# msp430.net
KiCad netlist of a schematic drawn in Altium Designer
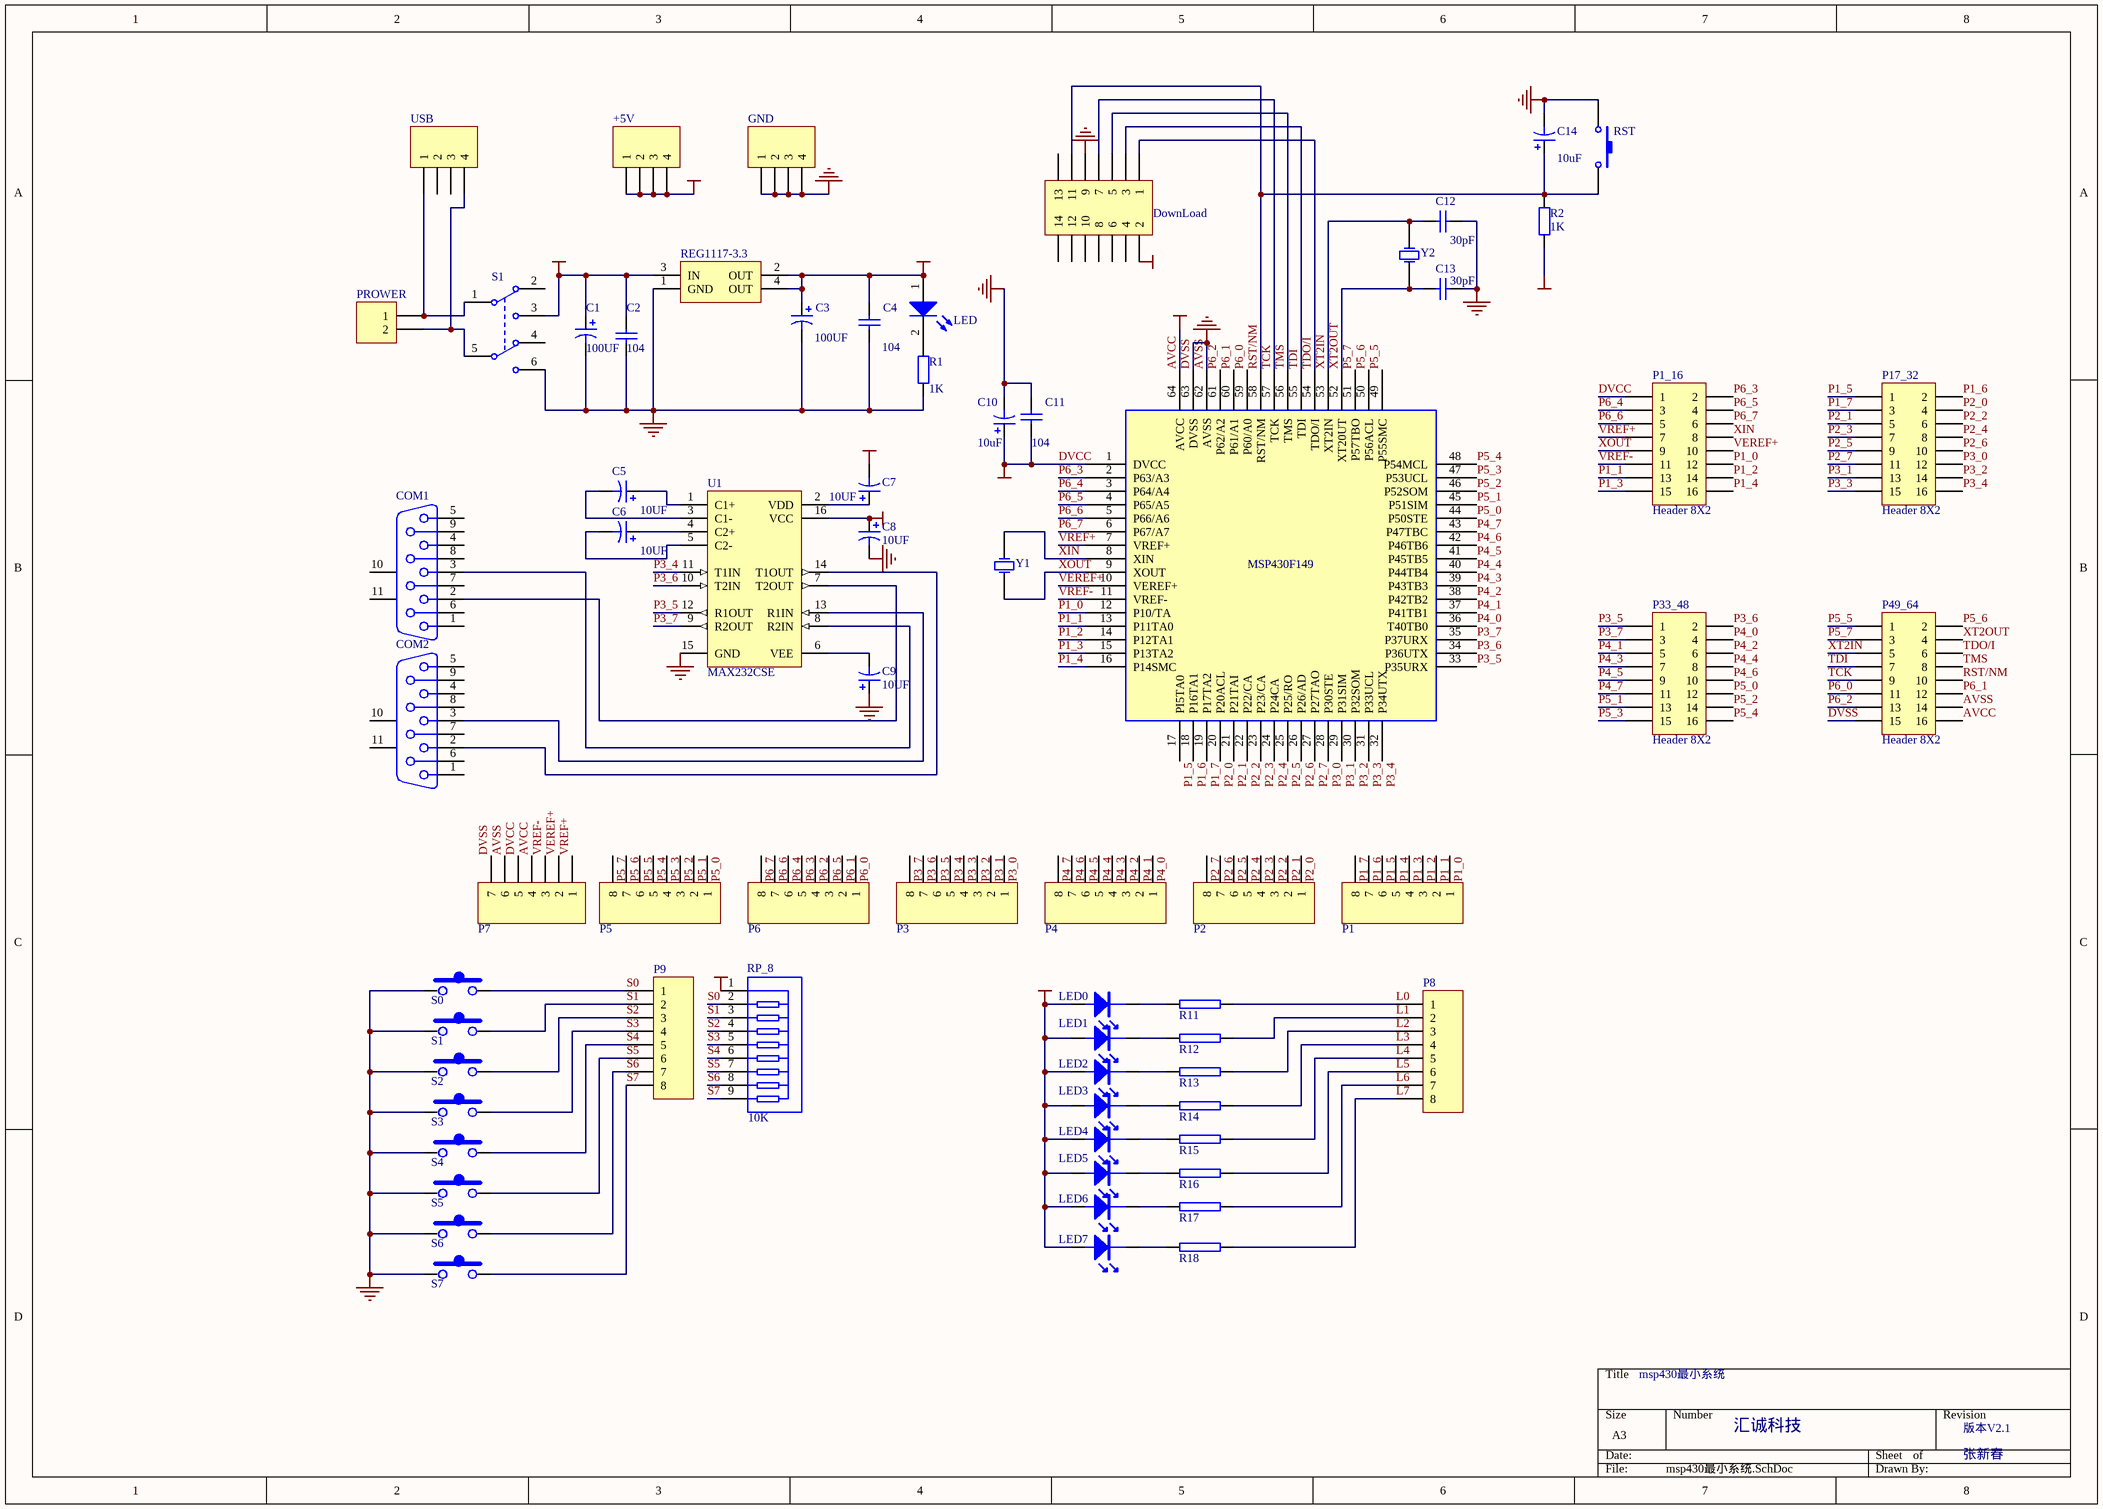
[diagram p0: msp430最小系统.SchDoc]

(export (version "E")
  (design (tool "Eeschema 10.0.6"))
  (components
    (comp (ref "+5V")
      (value "Header 4")
      (footprint "HDR1X4")
      (description "Header, 4-Pin")
      (fields (field (name "PUBLISHER") "Altium Limited"))
      (libsource (lib "Miscellaneous Connectors") (part "Header 4"))
    )
    (comp (ref "1") (value "S0") (footprint "an-6*6") (libsource (lib "OldCow1 (1)") (part "KEY")))
    (comp (ref "2") (value "S1") (footprint "an-6*6") (libsource (lib "OldCow1 (1)") (part "KEY")))
    (comp (ref "3") (value "S2") (footprint "an-6*6") (libsource (lib "OldCow1 (1)") (part "KEY")))
    (comp (ref "4") (value "S3") (footprint "an-6*6") (libsource (lib "OldCow1 (1)") (part "KEY")))
    (comp (ref "5") (value "S4") (footprint "an-6*6") (libsource (lib "OldCow1 (1)") (part "KEY")))
    (comp (ref "6") (value "S5") (footprint "an-6*6") (libsource (lib "OldCow1 (1)") (part "KEY")))
    (comp (ref "7") (value "S6") (footprint "an-6*6") (libsource (lib "OldCow1 (1)") (part "KEY")))
    (comp (ref "8") (value "S7") (footprint "an-6*6") (libsource (lib "OldCow1 (1)") (part "KEY")))
    (comp (ref "C1")
      (value "100UF")
      (footprint "C-DJ-6")
      (description "Polarized Capacitor (Radial)")
      (fields (field (name "Comment") "Cap Pol1") (field (name "PUBLISHER") "Altium Limited"))
      (libsource (lib "Miscellaneous Devices") (part "Cap Pol1"))
    )
    (comp (ref "C2")
      (value "104")
      (footprint "CPDR")
      (description "Capacitor (Semiconductor SIM Model)")
      (fields (field (name "Comment") "Cap Semi") (field (name "PUBLISHER") "Altium Limited"))
      (libsource (lib "Miscellaneous Devices") (part "Cap Semi"))
    )
    (comp (ref "C3")
      (value "100UF")
      (footprint "C-DJ-4")
      (description "Polarized Capacitor (Radial)")
      (fields (field (name "Comment") "Cap Pol1") (field (name "PUBLISHER") "Altium Limited"))
      (libsource (lib "Miscellaneous Devices") (part "Cap Pol1"))
    )
    (comp (ref "C4")
      (value "104")
      (footprint "CPDR")
      (description "Capacitor (Semiconductor SIM Model)")
      (fields (field (name "Comment") "Cap Semi") (field (name "PUBLISHER") "Altium Limited"))
      (libsource (lib "Miscellaneous Devices") (part "Cap Semi"))
    )
    (comp (ref "C5")
      (value "10UF")
      (footprint "C-DJ-4")
      (description "Polarized Capacitor (Radial)")
      (fields (field (name "Comment") "Cap Pol1") (field (name "PUBLISHER") "Altium Limited"))
      (libsource (lib "Miscellaneous Devices") (part "Cap Pol1"))
    )
    (comp (ref "C6")
      (value "10UF")
      (footprint "C-DJ-4")
      (description "Polarized Capacitor (Radial)")
      (fields (field (name "Comment") "Cap Pol1") (field (name "PUBLISHER") "Altium Limited"))
      (libsource (lib "Miscellaneous Devices") (part "Cap Pol1"))
    )
    (comp (ref "C7")
      (value "10UF")
      (footprint "C-DJ-4")
      (description "Polarized Capacitor (Radial)")
      (fields (field (name "Comment") "Cap Pol1") (field (name "PUBLISHER") "Altium Limited"))
      (libsource (lib "Miscellaneous Devices") (part "Cap Pol1"))
    )
    (comp (ref "C8")
      (value "10UF")
      (footprint "C-DJ-4")
      (description "Polarized Capacitor (Radial)")
      (fields (field (name "Comment") "Cap Pol1") (field (name "PUBLISHER") "Altium Limited"))
      (libsource (lib "Miscellaneous Devices") (part "Cap Pol1"))
    )
    (comp (ref "C9")
      (value "10UF")
      (footprint "C-DJ-4")
      (description "Polarized Capacitor (Radial)")
      (fields (field (name "Comment") "Cap Pol1") (field (name "PUBLISHER") "Altium Limited"))
      (libsource (lib "Miscellaneous Devices") (part "Cap Pol1"))
    )
    (comp (ref "C10")
      (value "10uF")
      (footprint "C-DJ-4")
      (description "Polarized Capacitor (Radial)")
      (fields (field (name "Comment") "Cap Pol1") (field (name "PUBLISHER") "Altium Limited"))
      (libsource (lib "Miscellaneous Devices") (part "Cap Pol1"))
    )
    (comp (ref "C11")
      (value "104")
      (footprint "CPDR")
      (description "Capacitor (Semiconductor SIM Model)")
      (fields (field (name "Comment") "Cap Semi") (field (name "PUBLISHER") "Altium Limited"))
      (libsource (lib "Miscellaneous Devices") (part "Cap Semi"))
    )
    (comp (ref "C12")
      (value "30pF")
      (footprint "CPDR")
      (description "瓷片电容")
      (fields (field (name "Comment") "CPDR") (field (name "PUBLISHER") "Altium Limited"))
      (libsource (lib "zxcourhc") (part "CPDR"))
    )
    (comp (ref "C13")
      (value "30pF")
      (footprint "CPDR")
      (description "瓷片电容")
      (fields (field (name "Comment") "CPDR") (field (name "PUBLISHER") "Altium Limited"))
      (libsource (lib "zxcourhc") (part "CPDR"))
    )
    (comp (ref "C14")
      (value "10uF")
      (footprint "C-DJ-4")
      (description "Polarized Capacitor (Radial)")
      (fields (field (name "Comment") "Cap Pol1") (field (name "PUBLISHER") "Altium Limited"))
      (libsource (lib "Miscellaneous Devices") (part "Cap Pol1"))
    )
    (comp (ref "COM1")
      (value "D Connector 9")
      (footprint "zxcourhc:COM-9")
      (description "Receptacle Assembly, 9 Position, Right Angle")
      (fields (field (name "PUBLISHER") "Altium Limited"))
      (libsource (lib "Miscellaneous Connectors") (part "D Connector 9"))
    )
    (comp (ref "COM2")
      (value "D Connector 9")
      (footprint "zxcourhc:COM-9")
      (description "Receptacle Assembly, 9 Position, Right Angle")
      (fields (field (name "PUBLISHER") "Altium Limited"))
      (libsource (lib "Miscellaneous Connectors") (part "D Connector 9"))
    )
    (comp (ref "DownLoad")
      (value "Header 7X2")
      (footprint "HDR-2X7")
      (description "Header, 7-Pin, Dual row")
      (fields (field (name "PUBLISHER") "Altium Limited"))
      (libsource (lib "Miscellaneous Connectors") (part "Header 7X2"))
    )
    (comp (ref "DS1")
      (value "LED")
      (footprint "LED")
      (description "发光二极管")
      (fields (field (name "PUBLISHER") "Altium Limited"))
      (libsource (lib "zxcourhc") (part "LED"))
    )
    (comp (ref "GND")
      (value "Header 4")
      (footprint "HDR1X4")
      (description "Header, 4-Pin")
      (fields (field (name "PUBLISHER") "Altium Limited"))
      (libsource (lib "Miscellaneous Connectors") (part "Header 4"))
    )
    (comp (ref "LED0") (value "LED") (footprint "TP-0805-D") (libsource (lib "OldCow1 (1)") (part "LED")))
    (comp (ref "LED1") (value "LED") (footprint "TP-0805-D") (libsource (lib "OldCow1 (1)") (part "LED")))
    (comp (ref "LED2") (value "LED") (footprint "TP-0805-D") (libsource (lib "OldCow1 (1)") (part "LED")))
    (comp (ref "LED3") (value "LED") (footprint "TP-0805-D") (libsource (lib "OldCow1 (1)") (part "LED")))
    (comp (ref "LED4") (value "LED") (footprint "TP-0805-D") (libsource (lib "OldCow1 (1)") (part "LED")))
    (comp (ref "LED5") (value "LED") (footprint "TP-0805-D") (libsource (lib "OldCow1 (1)") (part "LED")))
    (comp (ref "LED6") (value "LED") (footprint "TP-0805-D") (libsource (lib "OldCow1 (1)") (part "LED")))
    (comp (ref "LED7") (value "LED") (footprint "TP-0805-D") (libsource (lib "OldCow1 (1)") (part "LED")))
    (comp (ref "MSP430F149")
      (value "MSP430F149")
      (footprint "MPS430149")
      (libsource (lib "MyInt_Lib") (part "MSP430F133"))
    )
    (comp (ref "P1")
      (value "Header 8")
      (footprint "zxcourhc:HDR-8")
      (description "Header, 8-Pin")
      (fields (field (name "PUBLISHER") "Altium Limited"))
      (libsource (lib "Miscellaneous Connectors") (part "Header 8"))
    )
    (comp (ref "P1_16")
      (value "Header 8X2")
      (footprint "HDR2X8")
      (description "Header, 8-Pin, Dual row")
      (fields (field (name "PUBLISHER") "Altium Limited"))
      (libsource (lib "Miscellaneous Connectors") (part "Header 8X2"))
    )
    (comp (ref "P2")
      (value "Header 8")
      (footprint "zxcourhc:HD-8")
      (description "Header, 8-Pin")
      (fields (field (name "PUBLISHER") "Altium Limited"))
      (libsource (lib "Miscellaneous Connectors") (part "Header 8"))
    )
    (comp (ref "P3")
      (value "Header 8")
      (footprint "zxcourhc:HD-8")
      (description "Header, 8-Pin")
      (fields (field (name "PUBLISHER") "Altium Limited"))
      (libsource (lib "Miscellaneous Connectors") (part "Header 8"))
    )
    (comp (ref "P4")
      (value "Header 8")
      (footprint "zxcourhc:HD-8")
      (description "Header, 8-Pin")
      (fields (field (name "PUBLISHER") "Altium Limited"))
      (libsource (lib "Miscellaneous Connectors") (part "Header 8"))
    )
    (comp (ref "P5")
      (value "Header 8")
      (footprint "zxcourhc:HD-8")
      (description "Header, 8-Pin")
      (fields (field (name "PUBLISHER") "Altium Limited"))
      (libsource (lib "Miscellaneous Connectors") (part "Header 8"))
    )
    (comp (ref "P6")
      (value "Header 8")
      (footprint "zxcourhc:HD-8")
      (description "Header, 8-Pin")
      (fields (field (name "PUBLISHER") "Altium Limited"))
      (libsource (lib "Miscellaneous Connectors") (part "Header 8"))
    )
    (comp (ref "P7")
      (value "Header 7")
      (footprint "HDR1X7")
      (description "Header, 7-Pin")
      (fields (field (name "PUBLISHER") "Altium Limited"))
      (libsource (lib "Miscellaneous Connectors") (part "Header 7"))
    )
    (comp (ref "P8")
      (value "PZ_8")
      (footprint "HDR-8")
      (description "排针——8")
      (fields (field (name "PUBLISHER") "Altium Limited"))
      (libsource (lib "zxcourhc") (part "PZ_8"))
    )
    (comp (ref "P9")
      (value "PZ_8")
      (footprint "HDR-8")
      (description "排针——8")
      (fields (field (name "PUBLISHER") "Altium Limited"))
      (libsource (lib "zxcourhc") (part "PZ_8"))
    )
    (comp (ref "P17_32")
      (value "Header 8X2")
      (footprint "HDR2X8")
      (description "Header, 8-Pin, Dual row")
      (fields (field (name "PUBLISHER") "Altium Limited"))
      (libsource (lib "Miscellaneous Connectors") (part "Header 8X2"))
    )
    (comp (ref "P33_48")
      (value "Header 8X2")
      (footprint "HDR2X8")
      (description "Header, 8-Pin, Dual row")
      (fields (field (name "PUBLISHER") "Altium Limited"))
      (libsource (lib "Miscellaneous Connectors") (part "Header 8X2"))
    )
    (comp (ref "P49_64")
      (value "Header 8X2")
      (footprint "HDR2X8")
      (description "Header, 8-Pin, Dual row")
      (fields (field (name "PUBLISHER") "Altium Limited"))
      (libsource (lib "Miscellaneous Connectors") (part "Header 8X2"))
    )
    (comp (ref "PROWER")
      (value "PZ_2")
      (footprint "zxcourhc:JK128_2")
      (description "排针——2")
      (fields (field (name "PUBLISHER") "Altium Limited"))
      (libsource (lib "zxcourhc") (part "PZ_2"))
    )
    (comp (ref "R1")
      (value "1K")
      (footprint "TP-0805-R")
      (description "电阻")
      (fields (field (name "Comment") "Res") (field (name "PUBLISHER") "Altium Limited"))
      (libsource (lib "zxcourhc") (part "Res"))
    )
    (comp (ref "R2")
      (value "1K")
      (footprint "TP-0805-R")
      (description "电阻")
      (fields (field (name "Comment") "Res") (field (name "PUBLISHER") "Altium Limited"))
      (libsource (lib "zxcourhc") (part "Res"))
    )
    (comp (ref "R11") (value "RES1") (footprint "TP-0805-R") (libsource (lib "OldCow1 (1)") (part "RES1")))
    (comp (ref "R12") (value "RES1") (footprint "TP-0805-R") (libsource (lib "OldCow1 (1)") (part "RES1")))
    (comp (ref "R13") (value "RES1") (footprint "TP-0805-R") (libsource (lib "OldCow1 (1)") (part "RES1")))
    (comp (ref "R14") (value "RES1") (footprint "TP-0805-R") (libsource (lib "OldCow1 (1)") (part "RES1")))
    (comp (ref "R15") (value "RES1") (footprint "TP-0805-R") (libsource (lib "OldCow1 (1)") (part "RES1")))
    (comp (ref "R16") (value "RES1") (footprint "TP-0805-R") (libsource (lib "OldCow1 (1)") (part "RES1")))
    (comp (ref "R17") (value "RES1") (footprint "TP-0805-R") (libsource (lib "OldCow1 (1)") (part "RES1")))
    (comp (ref "R18") (value "RES1") (footprint "TP-0805-R") (libsource (lib "OldCow1 (1)") (part "RES1")))
    (comp (ref "REG1117-3.3")
      (value "REG1117-3.3")
      (footprint "ZZ311")
      (description "800mA and 1A Low Dropout Positive Regulator 2.85V, 3.3V, 5V, and Adjustable")
      (fields (field (name "PUBLISHER") "Altium Limited"))
      (libsource (lib "BB Power Mgt Voltage Regulator") (part "REG1117-3.3"))
    )
    (comp (ref "RP_8")
      (value "10K")
      (footprint "HDR-10")
      (description "8位排阻")
      (fields (field (name "Comment") "Res PZ_8") (field (name "PUBLISHER") "Altium Limited"))
      (libsource (lib "zxcourhc") (part "Res PZ_8"))
    )
    (comp (ref "RST")
      (value "AJKG")
      (footprint "an-6*6")
      (description "按键开关")
      (fields (field (name "PUBLISHER") "Altium Limited"))
      (libsource (lib "zxcourhc") (part "AJKG"))
    )
    (comp (ref "S1")
      (value "ZSKG_KEY")
      (footprint "zxcourhc:DPDT-6")
      (description "自锁开关")
      (fields (field (name "PUBLISHER") "Altium Limited"))
      (libsource (lib "zxcourhc") (part "ZSKG_KEY"))
    )
    (comp (ref "U1")
      (value "MAX232CSE")
      (footprint "DIP-16")
      (description "+5V Powered, Multi-Channel RS-232 Driver/Receiver")
      (fields (field (name "PUBLISHER") "Altium Limited"))
      (libsource (lib "Maxim Communication Transceiver") (part "MAX232CSE"))
    )
    (comp (ref "USB")
      (value "PZ_4")
      (footprint "zxcourhc:USB-5V")
      (description "排针——4")
      (fields (field (name "PUBLISHER") "Altium Limited"))
      (libsource (lib "zxcourhc") (part "PZ_4"))
    )
    (comp (ref "Y1")
      (value "XTAL")
      (footprint "BCY-W2/D3.1")
      (description "Crystal Oscillator")
      (fields (field (name "PUBLISHER") "Altium Limited"))
      (libsource (lib "Miscellaneous Devices") (part "XTAL"))
    )
    (comp (ref "Y2")
      (value "XTAL")
      (footprint "JZ_ZC")
      (description "Crystal Oscillator")
      (fields (field (name "PUBLISHER") "Altium Limited"))
      (libsource (lib "Miscellaneous Devices") (part "XTAL"))
    )
  )
  (nets
    (net (code "1") (name "+5V") (class "Default")
      (node (ref "+5V") (pin "1") (pinfunction "1_1") (pintype "passive"))
      (node (ref "+5V") (pin "2") (pinfunction "2_2") (pintype "passive"))
      (node (ref "+5V") (pin "3") (pinfunction "3_3") (pintype "passive"))
      (node (ref "+5V") (pin "4") (pinfunction "4_4") (pintype "passive"))
      (node (ref "C1") (pin "1") (pinfunction "1_1") (pintype "passive"))
      (node (ref "C2") (pin "2") (pinfunction "2_2") (pintype "passive"))
      (node (ref "C7") (pin "2") (pinfunction "2_2") (pintype "passive"))
      (node (ref "C8") (pin "1") (pinfunction "1_1") (pintype "passive"))
      (node (ref "REG1117-3.3") (pin "3") (pinfunction "IN_3") (pintype "power_in"))
      (node (ref "S1") (pin "3") (pinfunction "NO1_3") (pintype "passive"))
      (node (ref "U1") (pin "16") (pinfunction "VCC_16") (pintype "power_in"))
    )
    (net (code "2") (name "/L0") (class "Default")
      (node (ref "P8") (pin "1") (pinfunction "1_1") (pintype "passive"))
      (node (ref "R11") (pin "1") (pinfunction "1_1") (pintype "passive"))
    )
    (net (code "3") (name "/L1") (class "Default")
      (node (ref "P8") (pin "2") (pinfunction "2_2") (pintype "passive"))
      (node (ref "R12") (pin "1") (pinfunction "1_1") (pintype "passive"))
    )
    (net (code "4") (name "/L2") (class "Default")
      (node (ref "P8") (pin "3") (pinfunction "3_3") (pintype "passive"))
      (node (ref "R13") (pin "1") (pinfunction "1_1") (pintype "passive"))
    )
    (net (code "5") (name "/L3") (class "Default")
      (node (ref "P8") (pin "4") (pinfunction "4_4") (pintype "passive"))
      (node (ref "R14") (pin "1") (pinfunction "1_1") (pintype "passive"))
    )
    (net (code "6") (name "/L4") (class "Default")
      (node (ref "P8") (pin "5") (pinfunction "5_5") (pintype "passive"))
      (node (ref "R15") (pin "1") (pinfunction "1_1") (pintype "passive"))
    )
    (net (code "7") (name "/L5") (class "Default")
      (node (ref "P8") (pin "6") (pinfunction "6_6") (pintype "passive"))
      (node (ref "R16") (pin "1") (pinfunction "1_1") (pintype "passive"))
    )
    (net (code "8") (name "/L6") (class "Default")
      (node (ref "P8") (pin "7") (pinfunction "7_7") (pintype "passive"))
      (node (ref "R17") (pin "1") (pinfunction "1_1") (pintype "passive"))
    )
    (net (code "9") (name "/L7") (class "Default")
      (node (ref "P8") (pin "8") (pinfunction "8_8") (pintype "passive"))
      (node (ref "R18") (pin "1") (pinfunction "1_1") (pintype "passive"))
    )
    (net (code "10") (name "/P1_0") (class "Default")
      (node (ref "MSP430F149") (pin "12") (pinfunction "P10/TA_12") (pintype "passive"))
      (node (ref "P1") (pin "1") (pinfunction "1_1") (pintype "passive"))
      (node (ref "P1_16") (pin "12") (pinfunction "12_12") (pintype "passive"))
    )
    (net (code "11") (name "/P1_1") (class "Default")
      (node (ref "MSP430F149") (pin "13") (pinfunction "P11TA0_13") (pintype "passive"))
      (node (ref "P1") (pin "2") (pinfunction "2_2") (pintype "passive"))
      (node (ref "P1_16") (pin "13") (pinfunction "13_13") (pintype "passive"))
    )
    (net (code "12") (name "/P1_2") (class "Default")
      (node (ref "MSP430F149") (pin "14") (pinfunction "P12TA1_14") (pintype "passive"))
      (node (ref "P1") (pin "3") (pinfunction "3_3") (pintype "passive"))
      (node (ref "P1_16") (pin "14") (pinfunction "14_14") (pintype "passive"))
    )
    (net (code "13") (name "/P1_3") (class "Default")
      (node (ref "MSP430F149") (pin "15") (pinfunction "P13TA2_15") (pintype "passive"))
      (node (ref "P1") (pin "4") (pinfunction "4_4") (pintype "passive"))
      (node (ref "P1_16") (pin "15") (pinfunction "15_15") (pintype "passive"))
    )
    (net (code "14") (name "/P1_4") (class "Default")
      (node (ref "MSP430F149") (pin "16") (pinfunction "P14SMC_16") (pintype "passive"))
      (node (ref "P1") (pin "5") (pinfunction "5_5") (pintype "passive"))
      (node (ref "P1_16") (pin "16") (pinfunction "16_16") (pintype "passive"))
    )
    (net (code "15") (name "/P1_5") (class "Default")
      (node (ref "MSP430F149") (pin "17") (pinfunction "PI5TA0_17") (pintype "passive"))
      (node (ref "P1") (pin "6") (pinfunction "6_6") (pintype "passive"))
      (node (ref "P17_32") (pin "1") (pinfunction "1_1") (pintype "passive"))
    )
    (net (code "16") (name "/P1_6") (class "Default")
      (node (ref "MSP430F149") (pin "18") (pinfunction "P16TA1_18") (pintype "passive"))
      (node (ref "P1") (pin "7") (pinfunction "7_7") (pintype "passive"))
      (node (ref "P17_32") (pin "2") (pinfunction "2_2") (pintype "passive"))
    )
    (net (code "17") (name "/P1_7") (class "Default")
      (node (ref "MSP430F149") (pin "19") (pinfunction "P17TA2_19") (pintype "passive"))
      (node (ref "P1") (pin "8") (pinfunction "8_8") (pintype "passive"))
      (node (ref "P17_32") (pin "3") (pinfunction "3_3") (pintype "passive"))
    )
    (net (code "18") (name "/P2_0") (class "Default")
      (node (ref "MSP430F149") (pin "20") (pinfunction "P20ACL_20") (pintype "passive"))
      (node (ref "P17_32") (pin "4") (pinfunction "4_4") (pintype "passive"))
      (node (ref "P2") (pin "1") (pinfunction "1_1") (pintype "passive"))
    )
    (net (code "19") (name "/P2_1") (class "Default")
      (node (ref "MSP430F149") (pin "21") (pinfunction "P21TAI_21") (pintype "passive"))
      (node (ref "P17_32") (pin "5") (pinfunction "5_5") (pintype "passive"))
      (node (ref "P2") (pin "2") (pinfunction "2_2") (pintype "passive"))
    )
    (net (code "20") (name "/P2_2") (class "Default")
      (node (ref "MSP430F149") (pin "22") (pinfunction "P22/CA_22") (pintype "passive"))
      (node (ref "P17_32") (pin "6") (pinfunction "6_6") (pintype "passive"))
      (node (ref "P2") (pin "3") (pinfunction "3_3") (pintype "passive"))
    )
    (net (code "21") (name "/P2_3") (class "Default")
      (node (ref "MSP430F149") (pin "23") (pinfunction "P23/CA_23") (pintype "passive"))
      (node (ref "P17_32") (pin "7") (pinfunction "7_7") (pintype "passive"))
      (node (ref "P2") (pin "4") (pinfunction "4_4") (pintype "passive"))
    )
    (net (code "22") (name "/P2_4") (class "Default")
      (node (ref "MSP430F149") (pin "24") (pinfunction "P24CA_24") (pintype "passive"))
      (node (ref "P17_32") (pin "8") (pinfunction "8_8") (pintype "passive"))
      (node (ref "P2") (pin "5") (pinfunction "5_5") (pintype "passive"))
    )
    (net (code "23") (name "/P2_5") (class "Default")
      (node (ref "MSP430F149") (pin "25") (pinfunction "P25/RO_25") (pintype "passive"))
      (node (ref "P17_32") (pin "9") (pinfunction "9_9") (pintype "passive"))
      (node (ref "P2") (pin "6") (pinfunction "6_6") (pintype "passive"))
    )
    (net (code "24") (name "/P2_6") (class "Default")
      (node (ref "MSP430F149") (pin "26") (pinfunction "P26/AD_26") (pintype "passive"))
      (node (ref "P17_32") (pin "10") (pinfunction "10_10") (pintype "passive"))
      (node (ref "P2") (pin "7") (pinfunction "7_7") (pintype "passive"))
    )
    (net (code "25") (name "/P2_7") (class "Default")
      (node (ref "MSP430F149") (pin "27") (pinfunction "P27TAO_27") (pintype "passive"))
      (node (ref "P17_32") (pin "11") (pinfunction "11_11") (pintype "passive"))
      (node (ref "P2") (pin "8") (pinfunction "8_8") (pintype "passive"))
    )
    (net (code "26") (name "/P3_0") (class "Default")
      (node (ref "MSP430F149") (pin "28") (pinfunction "P30STE_28") (pintype "passive"))
      (node (ref "P17_32") (pin "12") (pinfunction "12_12") (pintype "passive"))
      (node (ref "P3") (pin "1") (pinfunction "1_1") (pintype "passive"))
    )
    (net (code "27") (name "/P3_1") (class "Default")
      (node (ref "MSP430F149") (pin "29") (pinfunction "P31SIM_29") (pintype "passive"))
      (node (ref "P17_32") (pin "13") (pinfunction "13_13") (pintype "passive"))
      (node (ref "P3") (pin "2") (pinfunction "2_2") (pintype "passive"))
    )
    (net (code "28") (name "/P3_2") (class "Default")
      (node (ref "MSP430F149") (pin "30") (pinfunction "P32SOM_30") (pintype "passive"))
      (node (ref "P17_32") (pin "14") (pinfunction "14_14") (pintype "passive"))
      (node (ref "P3") (pin "3") (pinfunction "3_3") (pintype "passive"))
    )
    (net (code "29") (name "/P3_3") (class "Default")
      (node (ref "MSP430F149") (pin "31") (pinfunction "P33UCL_31") (pintype "passive"))
      (node (ref "P17_32") (pin "15") (pinfunction "15_15") (pintype "passive"))
      (node (ref "P3") (pin "4") (pinfunction "4_4") (pintype "passive"))
    )
    (net (code "30") (name "/P3_4") (class "Default")
      (node (ref "MSP430F149") (pin "32") (pinfunction "P34UTX_32") (pintype "passive"))
      (node (ref "P17_32") (pin "16") (pinfunction "16_16") (pintype "passive"))
      (node (ref "P3") (pin "5") (pinfunction "5_5") (pintype "passive"))
      (node (ref "U1") (pin "11") (pinfunction "T1IN_11") (pintype "input"))
    )
    (net (code "31") (name "/P3_5") (class "Default")
      (node (ref "MSP430F149") (pin "33") (pinfunction "P35URX_33") (pintype "passive"))
      (node (ref "P3") (pin "6") (pinfunction "6_6") (pintype "passive"))
      (node (ref "P33_48") (pin "1") (pinfunction "1_1") (pintype "passive"))
      (node (ref "U1") (pin "12") (pinfunction "R1OUT_12") (pintype "output"))
    )
    (net (code "32") (name "/P3_6") (class "Default")
      (node (ref "MSP430F149") (pin "34") (pinfunction "P36UTX_34") (pintype "passive"))
      (node (ref "P3") (pin "7") (pinfunction "7_7") (pintype "passive"))
      (node (ref "P33_48") (pin "2") (pinfunction "2_2") (pintype "passive"))
      (node (ref "U1") (pin "10") (pinfunction "T2IN_10") (pintype "input"))
    )
    (net (code "33") (name "/P3_7") (class "Default")
      (node (ref "MSP430F149") (pin "35") (pinfunction "P37URX_35") (pintype "passive"))
      (node (ref "P3") (pin "8") (pinfunction "8_8") (pintype "passive"))
      (node (ref "P33_48") (pin "3") (pinfunction "3_3") (pintype "passive"))
      (node (ref "U1") (pin "9") (pinfunction "R2OUT_9") (pintype "output"))
    )
    (net (code "34") (name "/P4_0") (class "Default")
      (node (ref "MSP430F149") (pin "36") (pinfunction "T40TB0_36") (pintype "passive"))
      (node (ref "P33_48") (pin "4") (pinfunction "4_4") (pintype "passive"))
      (node (ref "P4") (pin "1") (pinfunction "1_1") (pintype "passive"))
    )
    (net (code "35") (name "/P4_1") (class "Default")
      (node (ref "MSP430F149") (pin "37") (pinfunction "P41TB1_37") (pintype "passive"))
      (node (ref "P33_48") (pin "5") (pinfunction "5_5") (pintype "passive"))
      (node (ref "P4") (pin "2") (pinfunction "2_2") (pintype "passive"))
    )
    (net (code "36") (name "/P4_2") (class "Default")
      (node (ref "MSP430F149") (pin "38") (pinfunction "P42TB2_38") (pintype "passive"))
      (node (ref "P33_48") (pin "6") (pinfunction "6_6") (pintype "passive"))
      (node (ref "P4") (pin "3") (pinfunction "3_3") (pintype "passive"))
    )
    (net (code "37") (name "/P4_3") (class "Default")
      (node (ref "MSP430F149") (pin "39") (pinfunction "P43TB3_39") (pintype "passive"))
      (node (ref "P33_48") (pin "7") (pinfunction "7_7") (pintype "passive"))
      (node (ref "P4") (pin "4") (pinfunction "4_4") (pintype "passive"))
    )
    (net (code "38") (name "/P4_4") (class "Default")
      (node (ref "MSP430F149") (pin "40") (pinfunction "P44TB4_40") (pintype "passive"))
      (node (ref "P33_48") (pin "8") (pinfunction "8_8") (pintype "passive"))
      (node (ref "P4") (pin "5") (pinfunction "5_5") (pintype "passive"))
    )
    (net (code "39") (name "/P4_5") (class "Default")
      (node (ref "MSP430F149") (pin "41") (pinfunction "P45TB5_41") (pintype "passive"))
      (node (ref "P33_48") (pin "9") (pinfunction "9_9") (pintype "passive"))
      (node (ref "P4") (pin "6") (pinfunction "6_6") (pintype "passive"))
    )
    (net (code "40") (name "/P4_6") (class "Default")
      (node (ref "MSP430F149") (pin "42") (pinfunction "P46TB6_42") (pintype "passive"))
      (node (ref "P33_48") (pin "10") (pinfunction "10_10") (pintype "passive"))
      (node (ref "P4") (pin "7") (pinfunction "7_7") (pintype "passive"))
    )
    (net (code "41") (name "/P4_7") (class "Default")
      (node (ref "MSP430F149") (pin "43") (pinfunction "P47TBC_43") (pintype "passive"))
      (node (ref "P33_48") (pin "11") (pinfunction "11_11") (pintype "passive"))
      (node (ref "P4") (pin "8") (pinfunction "8_8") (pintype "passive"))
    )
    (net (code "42") (name "/P5_0") (class "Default")
      (node (ref "MSP430F149") (pin "44") (pinfunction "P50STE_44") (pintype "passive"))
      (node (ref "P33_48") (pin "12") (pinfunction "12_12") (pintype "passive"))
      (node (ref "P5") (pin "1") (pinfunction "1_1") (pintype "passive"))
    )
    (net (code "43") (name "/P5_1") (class "Default")
      (node (ref "MSP430F149") (pin "45") (pinfunction "P51SIM_45") (pintype "passive"))
      (node (ref "P33_48") (pin "13") (pinfunction "13_13") (pintype "passive"))
      (node (ref "P5") (pin "2") (pinfunction "2_2") (pintype "passive"))
    )
    (net (code "44") (name "/P5_2") (class "Default")
      (node (ref "MSP430F149") (pin "46") (pinfunction "P52SOM_46") (pintype "passive"))
      (node (ref "P33_48") (pin "14") (pinfunction "14_14") (pintype "passive"))
      (node (ref "P5") (pin "3") (pinfunction "3_3") (pintype "passive"))
    )
    (net (code "45") (name "/P5_3") (class "Default")
      (node (ref "MSP430F149") (pin "47") (pinfunction "P53UCL_47") (pintype "passive"))
      (node (ref "P33_48") (pin "15") (pinfunction "15_15") (pintype "passive"))
      (node (ref "P5") (pin "4") (pinfunction "4_4") (pintype "passive"))
    )
    (net (code "46") (name "/P5_4") (class "Default")
      (node (ref "MSP430F149") (pin "48") (pinfunction "P54MCL_48") (pintype "passive"))
      (node (ref "P33_48") (pin "16") (pinfunction "16_16") (pintype "passive"))
      (node (ref "P5") (pin "5") (pinfunction "5_5") (pintype "passive"))
    )
    (net (code "47") (name "/P5_5") (class "Default")
      (node (ref "MSP430F149") (pin "49") (pinfunction "P55SMC_49") (pintype "passive"))
      (node (ref "P49_64") (pin "1") (pinfunction "1_1") (pintype "passive"))
      (node (ref "P5") (pin "6") (pinfunction "6_6") (pintype "passive"))
    )
    (net (code "48") (name "/P5_6") (class "Default")
      (node (ref "MSP430F149") (pin "50") (pinfunction "P56ACL_50") (pintype "passive"))
      (node (ref "P49_64") (pin "2") (pinfunction "2_2") (pintype "passive"))
      (node (ref "P5") (pin "7") (pinfunction "7_7") (pintype "passive"))
    )
    (net (code "49") (name "/P5_7") (class "Default")
      (node (ref "MSP430F149") (pin "51") (pinfunction "P57TBO_51") (pintype "passive"))
      (node (ref "P49_64") (pin "3") (pinfunction "3_3") (pintype "passive"))
      (node (ref "P5") (pin "8") (pinfunction "8_8") (pintype "passive"))
    )
    (net (code "50") (name "/P6_0") (class "Default")
      (node (ref "MSP430F149") (pin "59") (pinfunction "P60/A0_59") (pintype "passive"))
      (node (ref "P49_64") (pin "11") (pinfunction "11_11") (pintype "passive"))
      (node (ref "P6") (pin "1") (pinfunction "1_1") (pintype "passive"))
    )
    (net (code "51") (name "/P6_1") (class "Default")
      (node (ref "MSP430F149") (pin "60") (pinfunction "P61/A1_60") (pintype "passive"))
      (node (ref "P49_64") (pin "12") (pinfunction "12_12") (pintype "passive"))
      (node (ref "P6") (pin "2") (pinfunction "2_2") (pintype "passive"))
    )
    (net (code "52") (name "/P6_2") (class "Default")
      (node (ref "MSP430F149") (pin "61") (pinfunction "P62/A2_61") (pintype "passive"))
      (node (ref "P49_64") (pin "13") (pinfunction "13_13") (pintype "passive"))
      (node (ref "P6") (pin "4") (pinfunction "4_4") (pintype "passive"))
    )
    (net (code "53") (name "/P6_3") (class "Default")
      (node (ref "MSP430F149") (pin "2") (pinfunction "P63/A3_2") (pintype "passive"))
      (node (ref "P1_16") (pin "2") (pinfunction "2_2") (pintype "passive"))
      (node (ref "P6") (pin "5") (pinfunction "5_5") (pintype "passive"))
    )
    (net (code "54") (name "/P6_4") (class "Default")
      (node (ref "MSP430F149") (pin "3") (pinfunction "P64/A4_3") (pintype "passive"))
      (node (ref "P1_16") (pin "3") (pinfunction "3_3") (pintype "passive"))
      (node (ref "P6") (pin "6") (pinfunction "6_6") (pintype "passive"))
    )
    (net (code "55") (name "/P6_5") (class "Default")
      (node (ref "MSP430F149") (pin "4") (pinfunction "P65/A5_4") (pintype "passive"))
      (node (ref "P1_16") (pin "4") (pinfunction "4_4") (pintype "passive"))
      (node (ref "P6") (pin "3") (pinfunction "3_3") (pintype "passive"))
    )
    (net (code "56") (name "/P6_6") (class "Default")
      (node (ref "MSP430F149") (pin "5") (pinfunction "P66/A6_5") (pintype "passive"))
      (node (ref "P1_16") (pin "5") (pinfunction "5_5") (pintype "passive"))
      (node (ref "P6") (pin "7") (pinfunction "7_7") (pintype "passive"))
    )
    (net (code "57") (name "/P6_7") (class "Default")
      (node (ref "MSP430F149") (pin "6") (pinfunction "P67/A7_6") (pintype "passive"))
      (node (ref "P1_16") (pin "6") (pinfunction "6_6") (pintype "passive"))
      (node (ref "P6") (pin "8") (pinfunction "8_8") (pintype "passive"))
    )
    (net (code "58") (name "/RST{slash}NM") (class "Default")
      (node (ref "C14") (pin "1") (pinfunction "1_1") (pintype "passive"))
      (node (ref "DownLoad") (pin "11") (pinfunction "11_11") (pintype "passive"))
      (node (ref "MSP430F149") (pin "58") (pinfunction "RST/NM_58") (pintype "passive"))
      (node (ref "P49_64") (pin "10") (pinfunction "10_10") (pintype "passive"))
      (node (ref "R2") (pin "2") (pinfunction "2_2") (pintype "passive"))
      (node (ref "RST") (pin "2") (pinfunction "2_2") (pintype "passive"))
    )
    (net (code "59") (name "/S0") (class "Default")
      (node (ref "1") (pin "2") (pinfunction "2_2") (pintype "passive"))
      (node (ref "P9") (pin "1") (pinfunction "1_1") (pintype "passive"))
      (node (ref "RP_8") (pin "2") (pinfunction "2_2") (pintype "passive"))
    )
    (net (code "60") (name "/S1") (class "Default")
      (node (ref "2") (pin "2") (pinfunction "2_2") (pintype "passive"))
      (node (ref "P9") (pin "2") (pinfunction "2_2") (pintype "passive"))
      (node (ref "RP_8") (pin "3") (pinfunction "3_3") (pintype "passive"))
    )
    (net (code "61") (name "/S2") (class "Default")
      (node (ref "3") (pin "2") (pinfunction "2_2") (pintype "passive"))
      (node (ref "P9") (pin "3") (pinfunction "3_3") (pintype "passive"))
      (node (ref "RP_8") (pin "4") (pinfunction "4_4") (pintype "passive"))
    )
    (net (code "62") (name "/S3") (class "Default")
      (node (ref "4") (pin "2") (pinfunction "2_2") (pintype "passive"))
      (node (ref "P9") (pin "4") (pinfunction "4_4") (pintype "passive"))
      (node (ref "RP_8") (pin "5") (pinfunction "5_5") (pintype "passive"))
    )
    (net (code "63") (name "/S4") (class "Default")
      (node (ref "5") (pin "2") (pinfunction "2_2") (pintype "passive"))
      (node (ref "P9") (pin "5") (pinfunction "5_5") (pintype "passive"))
      (node (ref "RP_8") (pin "6") (pinfunction "6_6") (pintype "passive"))
    )
    (net (code "64") (name "/S5") (class "Default")
      (node (ref "6") (pin "2") (pinfunction "2_2") (pintype "passive"))
      (node (ref "P9") (pin "6") (pinfunction "6_6") (pintype "passive"))
      (node (ref "RP_8") (pin "7") (pinfunction "7_7") (pintype "passive"))
    )
    (net (code "65") (name "/S6") (class "Default")
      (node (ref "7") (pin "2") (pinfunction "2_2") (pintype "passive"))
      (node (ref "P9") (pin "7") (pinfunction "7_7") (pintype "passive"))
      (node (ref "RP_8") (pin "8") (pinfunction "8_8") (pintype "passive"))
    )
    (net (code "66") (name "/S7") (class "Default")
      (node (ref "8") (pin "2") (pinfunction "2_2") (pintype "passive"))
      (node (ref "P9") (pin "8") (pinfunction "8_8") (pintype "passive"))
      (node (ref "RP_8") (pin "9") (pinfunction "9_9") (pintype "passive"))
    )
    (net (code "67") (name "/TCK") (class "Default")
      (node (ref "DownLoad") (pin "7") (pinfunction "7_7") (pintype "passive"))
      (node (ref "MSP430F149") (pin "57") (pinfunction "TCK_57") (pintype "passive"))
      (node (ref "P49_64") (pin "9") (pinfunction "9_9") (pintype "passive"))
    )
    (net (code "68") (name "/TDI") (class "Default")
      (node (ref "DownLoad") (pin "3") (pinfunction "3_3") (pintype "passive"))
      (node (ref "MSP430F149") (pin "55") (pinfunction "TDI_55") (pintype "passive"))
      (node (ref "P49_64") (pin "7") (pinfunction "7_7") (pintype "passive"))
    )
    (net (code "69") (name "/TDO{slash}I") (class "Default")
      (node (ref "DownLoad") (pin "1") (pinfunction "1_1") (pintype "passive"))
      (node (ref "MSP430F149") (pin "54") (pinfunction "TDO/I_54") (pintype "passive"))
      (node (ref "P49_64") (pin "6") (pinfunction "6_6") (pintype "passive"))
    )
    (net (code "70") (name "/TMS") (class "Default")
      (node (ref "DownLoad") (pin "5") (pinfunction "5_5") (pintype "passive"))
      (node (ref "MSP430F149") (pin "56") (pinfunction "TMS_56") (pintype "passive"))
      (node (ref "P49_64") (pin "8") (pinfunction "8_8") (pintype "passive"))
    )
    (net (code "71") (name "/VEREF+") (class "Default")
      (node (ref "MSP430F149") (pin "10") (pinfunction "VEREF+_10") (pintype "passive"))
      (node (ref "P1_16") (pin "10") (pinfunction "10_10") (pintype "passive"))
      (node (ref "P7") (pin "2") (pinfunction "2_2") (pintype "passive"))
    )
    (net (code "72") (name "/VREF+") (class "Default")
      (node (ref "MSP430F149") (pin "7") (pinfunction "VREF+_7") (pintype "passive"))
      (node (ref "P1_16") (pin "7") (pinfunction "7_7") (pintype "passive"))
      (node (ref "P7") (pin "1") (pinfunction "1_1") (pintype "passive"))
    )
    (net (code "73") (name "/VREF-") (class "Default")
      (node (ref "MSP430F149") (pin "11") (pinfunction "VREF-_11") (pintype "passive"))
      (node (ref "P1_16") (pin "11") (pinfunction "11_11") (pintype "passive"))
      (node (ref "P7") (pin "3") (pinfunction "3_3") (pintype "passive"))
    )
    (net (code "74") (name "/XIN") (class "Default")
      (node (ref "MSP430F149") (pin "8") (pinfunction "XIN_8") (pintype "passive"))
      (node (ref "P1_16") (pin "8") (pinfunction "8_8") (pintype "passive"))
      (node (ref "Y1") (pin "1") (pinfunction "OSC1_1") (pintype "passive"))
    )
    (net (code "75") (name "/XOUT") (class "Default")
      (node (ref "MSP430F149") (pin "9") (pinfunction "XOUT_9") (pintype "passive"))
      (node (ref "P1_16") (pin "9") (pinfunction "9_9") (pintype "passive"))
      (node (ref "Y1") (pin "2") (pinfunction "OSC2_2") (pintype "passive"))
    )
    (net (code "76") (name "/XT2IN") (class "Default")
      (node (ref "C12") (pin "1") (pinfunction "1_1") (pintype "passive"))
      (node (ref "MSP430F149") (pin "53") (pinfunction "XT2IN_53") (pintype "passive"))
      (node (ref "P49_64") (pin "5") (pinfunction "5_5") (pintype "passive"))
      (node (ref "Y2") (pin "2") (pinfunction "OSC2_2") (pintype "passive"))
    )
    (net (code "77") (name "/XT2OUT") (class "Default")
      (node (ref "C13") (pin "1") (pinfunction "1_1") (pintype "passive"))
      (node (ref "MSP430F149") (pin "52") (pinfunction "XT20UT_52") (pintype "passive"))
      (node (ref "P49_64") (pin "4") (pinfunction "4_4") (pintype "passive"))
      (node (ref "Y2") (pin "1") (pinfunction "OSC1_1") (pintype "passive"))
    )
    (net (code "78") (name "GND") (class "Default")
      (node (ref "1") (pin "1") (pinfunction "1_1") (pintype "passive"))
      (node (ref "2") (pin "1") (pinfunction "1_1") (pintype "passive"))
      (node (ref "3") (pin "1") (pinfunction "1_1") (pintype "passive"))
      (node (ref "4") (pin "1") (pinfunction "1_1") (pintype "passive"))
      (node (ref "5") (pin "1") (pinfunction "1_1") (pintype "passive"))
      (node (ref "6") (pin "1") (pinfunction "1_1") (pintype "passive"))
      (node (ref "7") (pin "1") (pinfunction "1_1") (pintype "passive"))
      (node (ref "8") (pin "1") (pinfunction "1_1") (pintype "passive"))
      (node (ref "C1") (pin "2") (pinfunction "2_2") (pintype "passive"))
      (node (ref "C10") (pin "2") (pinfunction "2_2") (pintype "passive"))
      (node (ref "C11") (pin "2") (pinfunction "2_2") (pintype "passive"))
      (node (ref "C12") (pin "2") (pinfunction "2_2") (pintype "passive"))
      (node (ref "C13") (pin "2") (pinfunction "2_2") (pintype "passive"))
      (node (ref "C14") (pin "2") (pinfunction "2_2") (pintype "passive"))
      (node (ref "C2") (pin "1") (pinfunction "1_1") (pintype "passive"))
      (node (ref "C3") (pin "2") (pinfunction "2_2") (pintype "passive"))
      (node (ref "C4") (pin "1") (pinfunction "1_1") (pintype "passive"))
      (node (ref "C8") (pin "2") (pinfunction "2_2") (pintype "passive"))
      (node (ref "C9") (pin "1") (pinfunction "1_1") (pintype "passive"))
      (node (ref "DownLoad") (pin "9") (pinfunction "9_9") (pintype "passive"))
      (node (ref "GND") (pin "1") (pinfunction "1_1") (pintype "passive"))
      (node (ref "GND") (pin "2") (pinfunction "2_2") (pintype "passive"))
      (node (ref "GND") (pin "3") (pinfunction "3_3") (pintype "passive"))
      (node (ref "GND") (pin "4") (pinfunction "4_4") (pintype "passive"))
      (node (ref "MSP430F149") (pin "62") (pinfunction "AVSS_62") (pintype "passive"))
      (node (ref "MSP430F149") (pin "63") (pinfunction "DVSS_63") (pintype "passive"))
      (node (ref "P49_64") (pin "14") (pinfunction "14_14") (pintype "passive"))
      (node (ref "P49_64") (pin "15") (pinfunction "15_15") (pintype "passive"))
      (node (ref "P7") (pin "6") (pinfunction "6_6") (pintype "passive"))
      (node (ref "P7") (pin "7") (pinfunction "7_7") (pintype "passive"))
      (node (ref "R1") (pin "1") (pinfunction "1_1") (pintype "passive"))
      (node (ref "REG1117-3.3") (pin "1") (pinfunction "GND_1") (pintype "power_in"))
      (node (ref "RST") (pin "1") (pinfunction "1_1") (pintype "passive"))
      (node (ref "S1") (pin "6") (pinfunction "NO2_6") (pintype "passive"))
      (node (ref "U1") (pin "15") (pinfunction "GND_15") (pintype "power_in"))
    )
    (net (code "79") (name "Net-(DS1-K)") (class "Default")
      (node (ref "DS1") (pin "2") (pinfunction "K_2") (pintype "passive"))
      (node (ref "R1") (pin "2") (pinfunction "2_2") (pintype "passive"))
    )
    (net (code "80") (name "Net-(LED0-K)") (class "Default")
      (node (ref "LED0") (pin "2") (pinfunction "K_2") (pintype "passive"))
      (node (ref "R11") (pin "2") (pinfunction "2_2") (pintype "passive"))
    )
    (net (code "81") (name "Net-(LED1-K)") (class "Default")
      (node (ref "LED1") (pin "2") (pinfunction "K_2") (pintype "passive"))
      (node (ref "R12") (pin "2") (pinfunction "2_2") (pintype "passive"))
    )
    (net (code "82") (name "Net-(LED2-K)") (class "Default")
      (node (ref "LED2") (pin "2") (pinfunction "K_2") (pintype "passive"))
      (node (ref "R13") (pin "2") (pinfunction "2_2") (pintype "passive"))
    )
    (net (code "83") (name "Net-(LED3-K)") (class "Default")
      (node (ref "LED3") (pin "2") (pinfunction "K_2") (pintype "passive"))
      (node (ref "R14") (pin "2") (pinfunction "2_2") (pintype "passive"))
    )
    (net (code "84") (name "Net-(LED4-K)") (class "Default")
      (node (ref "LED4") (pin "2") (pinfunction "K_2") (pintype "passive"))
      (node (ref "R15") (pin "2") (pinfunction "2_2") (pintype "passive"))
    )
    (net (code "85") (name "Net-(LED5-K)") (class "Default")
      (node (ref "LED5") (pin "2") (pinfunction "K_2") (pintype "passive"))
      (node (ref "R16") (pin "2") (pinfunction "2_2") (pintype "passive"))
    )
    (net (code "86") (name "Net-(LED6-K)") (class "Default")
      (node (ref "LED6") (pin "2") (pinfunction "K_2") (pintype "passive"))
      (node (ref "R17") (pin "2") (pinfunction "2_2") (pintype "passive"))
    )
    (net (code "87") (name "Net-(LED7-K)") (class "Default")
      (node (ref "LED7") (pin "2") (pinfunction "K_2") (pintype "passive"))
      (node (ref "R18") (pin "2") (pinfunction "2_2") (pintype "passive"))
    )
    (net (code "88") (name "Net-(S1-COMMON1)") (class "Default")
      (node (ref "PROWER") (pin "1") (pinfunction "1_1") (pintype "passive"))
      (node (ref "S1") (pin "1") (pinfunction "COMMON1_1") (pintype "passive"))
      (node (ref "USB") (pin "1") (pinfunction "1_1") (pintype "passive"))
    )
    (net (code "89") (name "Net-(S1-COMMON2)") (class "Default")
      (node (ref "PROWER") (pin "2") (pinfunction "2_2") (pintype "passive"))
      (node (ref "S1") (pin "5") (pinfunction "COMMON2_5") (pintype "passive"))
      (node (ref "USB") (pin "4") (pinfunction "4_4") (pintype "passive"))
    )
    (net (code "90") (name "Net-(U1-C1+)") (class "Default")
      (node (ref "C5") (pin "1") (pinfunction "1_1") (pintype "passive"))
      (node (ref "U1") (pin "1") (pinfunction "C1+_1") (pintype "passive"))
    )
    (net (code "91") (name "Net-(U1-C1-)") (class "Default")
      (node (ref "C5") (pin "2") (pinfunction "2_2") (pintype "passive"))
      (node (ref "U1") (pin "3") (pinfunction "C1-_3") (pintype "passive"))
    )
    (net (code "92") (name "Net-(U1-C2+)") (class "Default")
      (node (ref "C6") (pin "1") (pinfunction "1_1") (pintype "passive"))
      (node (ref "U1") (pin "4") (pinfunction "C2+_4") (pintype "passive"))
    )
    (net (code "93") (name "Net-(U1-C2-)") (class "Default")
      (node (ref "C6") (pin "2") (pinfunction "2_2") (pintype "passive"))
      (node (ref "U1") (pin "5") (pinfunction "C2-_5") (pintype "passive"))
    )
    (net (code "94") (name "Net-(U1-R1IN)") (class "Default")
      (node (ref "COM2") (pin "3") (pinfunction "3_3") (pintype "passive"))
      (node (ref "U1") (pin "13") (pinfunction "R1IN_13") (pintype "input"))
    )
    (net (code "95") (name "Net-(U1-R2IN)") (class "Default")
      (node (ref "COM1") (pin "3") (pinfunction "3_3") (pintype "passive"))
      (node (ref "U1") (pin "8") (pinfunction "R2IN_8") (pintype "input"))
    )
    (net (code "96") (name "Net-(U1-T1OUT)") (class "Default")
      (node (ref "COM2") (pin "2") (pinfunction "2_2") (pintype "passive"))
      (node (ref "U1") (pin "14") (pinfunction "T1OUT_14") (pintype "output"))
    )
    (net (code "97") (name "Net-(U1-T2OUT)") (class "Default")
      (node (ref "COM1") (pin "2") (pinfunction "2_2") (pintype "passive"))
      (node (ref "U1") (pin "7") (pinfunction "T2OUT_7") (pintype "output"))
    )
    (net (code "98") (name "Net-(U1-VDD)") (class "Default")
      (node (ref "C7") (pin "1") (pinfunction "1_1") (pintype "passive"))
      (node (ref "U1") (pin "2") (pinfunction "VDD_2") (pintype "power_in"))
    )
    (net (code "99") (name "Net-(U1-VEE)") (class "Default")
      (node (ref "C9") (pin "2") (pinfunction "2_2") (pintype "passive"))
      (node (ref "U1") (pin "6") (pinfunction "VEE_6") (pintype "power_in"))
    )
    (net (code "100") (name "VCC") (class "Default")
      (node (ref "C10") (pin "1") (pinfunction "1_1") (pintype "passive"))
      (node (ref "C11") (pin "1") (pinfunction "1_1") (pintype "passive"))
      (node (ref "C3") (pin "1") (pinfunction "1_1") (pintype "passive"))
      (node (ref "C4") (pin "2") (pinfunction "2_2") (pintype "passive"))
      (node (ref "DS1") (pin "1") (pinfunction "A_1") (pintype "passive"))
      (node (ref "DownLoad") (pin "2") (pinfunction "2_2") (pintype "passive"))
      (node (ref "LED0") (pin "1") (pinfunction "A_1") (pintype "passive"))
      (node (ref "LED1") (pin "1") (pinfunction "A_1") (pintype "passive"))
      (node (ref "LED2") (pin "1") (pinfunction "A_1") (pintype "passive"))
      (node (ref "LED3") (pin "1") (pinfunction "A_1") (pintype "passive"))
      (node (ref "LED4") (pin "1") (pinfunction "A_1") (pintype "passive"))
      (node (ref "LED5") (pin "1") (pinfunction "A_1") (pintype "passive"))
      (node (ref "LED6") (pin "1") (pinfunction "A_1") (pintype "passive"))
      (node (ref "LED7") (pin "1") (pinfunction "A_1") (pintype "passive"))
      (node (ref "MSP430F149") (pin "1") (pinfunction "DVCC_1") (pintype "passive"))
      (node (ref "MSP430F149") (pin "64") (pinfunction "AVCC_64") (pintype "passive"))
      (node (ref "P1_16") (pin "1") (pinfunction "1_1") (pintype "passive"))
      (node (ref "P49_64") (pin "16") (pinfunction "16_16") (pintype "passive"))
      (node (ref "P7") (pin "4") (pinfunction "4_4") (pintype "passive"))
      (node (ref "P7") (pin "5") (pinfunction "5_5") (pintype "passive"))
      (node (ref "R2") (pin "1") (pinfunction "1_1") (pintype "passive"))
      (node (ref "REG1117-3.3") (pin "2") (pinfunction "OUT_2") (pintype "power_in"))
      (node (ref "REG1117-3.3") (pin "4") (pinfunction "OUT_4") (pintype "power_in"))
      (node (ref "RP_8") (pin "1") (pinfunction "1_1") (pintype "passive"))
    )
    (net (code "101") (name "unconnected-(COM1-MH1-Pad10)") (class "Default")
      (node (ref "COM1") (pin "10") (pinfunction "MH1_10") (pintype "passive"))
    )
    (net (code "102") (name "unconnected-(COM1-MH2-Pad11)") (class "Default")
      (node (ref "COM1") (pin "11") (pinfunction "MH2_11") (pintype "passive"))
    )
    (net (code "103") (name "unconnected-(COM1-Pad1)") (class "Default")
      (node (ref "COM1") (pin "1") (pinfunction "1_1") (pintype "passive"))
    )
    (net (code "104") (name "unconnected-(COM1-Pad4)") (class "Default")
      (node (ref "COM1") (pin "4") (pinfunction "4_4") (pintype "passive"))
    )
    (net (code "105") (name "unconnected-(COM1-Pad5)") (class "Default")
      (node (ref "COM1") (pin "5") (pinfunction "5_5") (pintype "passive"))
    )
    (net (code "106") (name "unconnected-(COM1-Pad6)") (class "Default")
      (node (ref "COM1") (pin "6") (pinfunction "6_6") (pintype "passive"))
    )
    (net (code "107") (name "unconnected-(COM1-Pad7)") (class "Default")
      (node (ref "COM1") (pin "7") (pinfunction "7_7") (pintype "passive"))
    )
    (net (code "108") (name "unconnected-(COM1-Pad8)") (class "Default")
      (node (ref "COM1") (pin "8") (pinfunction "8_8") (pintype "passive"))
    )
    (net (code "109") (name "unconnected-(COM1-Pad9)") (class "Default")
      (node (ref "COM1") (pin "9") (pinfunction "9_9") (pintype "passive"))
    )
    (net (code "110") (name "unconnected-(COM2-MH1-Pad10)") (class "Default")
      (node (ref "COM2") (pin "10") (pinfunction "MH1_10") (pintype "passive"))
    )
    (net (code "111") (name "unconnected-(COM2-MH2-Pad11)") (class "Default")
      (node (ref "COM2") (pin "11") (pinfunction "MH2_11") (pintype "passive"))
    )
    (net (code "112") (name "unconnected-(COM2-Pad1)") (class "Default")
      (node (ref "COM2") (pin "1") (pinfunction "1_1") (pintype "passive"))
    )
    (net (code "113") (name "unconnected-(COM2-Pad4)") (class "Default")
      (node (ref "COM2") (pin "4") (pinfunction "4_4") (pintype "passive"))
    )
    (net (code "114") (name "unconnected-(COM2-Pad5)") (class "Default")
      (node (ref "COM2") (pin "5") (pinfunction "5_5") (pintype "passive"))
    )
    (net (code "115") (name "unconnected-(COM2-Pad6)") (class "Default")
      (node (ref "COM2") (pin "6") (pinfunction "6_6") (pintype "passive"))
    )
    (net (code "116") (name "unconnected-(COM2-Pad7)") (class "Default")
      (node (ref "COM2") (pin "7") (pinfunction "7_7") (pintype "passive"))
    )
    (net (code "117") (name "unconnected-(COM2-Pad8)") (class "Default")
      (node (ref "COM2") (pin "8") (pinfunction "8_8") (pintype "passive"))
    )
    (net (code "118") (name "unconnected-(COM2-Pad9)") (class "Default")
      (node (ref "COM2") (pin "9") (pinfunction "9_9") (pintype "passive"))
    )
    (net (code "119") (name "unconnected-(DownLoad-Pad4)") (class "Default")
      (node (ref "DownLoad") (pin "4") (pinfunction "4_4") (pintype "passive"))
    )
    (net (code "120") (name "unconnected-(DownLoad-Pad6)") (class "Default")
      (node (ref "DownLoad") (pin "6") (pinfunction "6_6") (pintype "passive"))
    )
    (net (code "121") (name "unconnected-(DownLoad-Pad8)") (class "Default")
      (node (ref "DownLoad") (pin "8") (pinfunction "8_8") (pintype "passive"))
    )
    (net (code "122") (name "unconnected-(DownLoad-Pad10)") (class "Default")
      (node (ref "DownLoad") (pin "10") (pinfunction "10_10") (pintype "passive"))
    )
    (net (code "123") (name "unconnected-(DownLoad-Pad12)") (class "Default")
      (node (ref "DownLoad") (pin "12") (pinfunction "12_12") (pintype "passive"))
    )
    (net (code "124") (name "unconnected-(DownLoad-Pad13)") (class "Default")
      (node (ref "DownLoad") (pin "13") (pinfunction "13_13") (pintype "passive"))
    )
    (net (code "125") (name "unconnected-(DownLoad-Pad14)") (class "Default")
      (node (ref "DownLoad") (pin "14") (pinfunction "14_14") (pintype "passive"))
    )
    (net (code "126") (name "unconnected-(S1-NC1-Pad2)") (class "Default")
      (node (ref "S1") (pin "2") (pinfunction "NC1_2") (pintype "passive"))
    )
    (net (code "127") (name "unconnected-(S1-NC2-Pad4)") (class "Default")
      (node (ref "S1") (pin "4") (pinfunction "NC2_4") (pintype "passive"))
    )
    (net (code "128") (name "unconnected-(USB-Pad2)") (class "Default")
      (node (ref "USB") (pin "2") (pinfunction "2_2") (pintype "passive"))
    )
    (net (code "129") (name "unconnected-(USB-Pad3)") (class "Default")
      (node (ref "USB") (pin "3") (pinfunction "3_3") (pintype "passive"))
    )
  )
)
